# POWER_RTC.net
KiCad netlist of a schematic drawn in Altium Designer
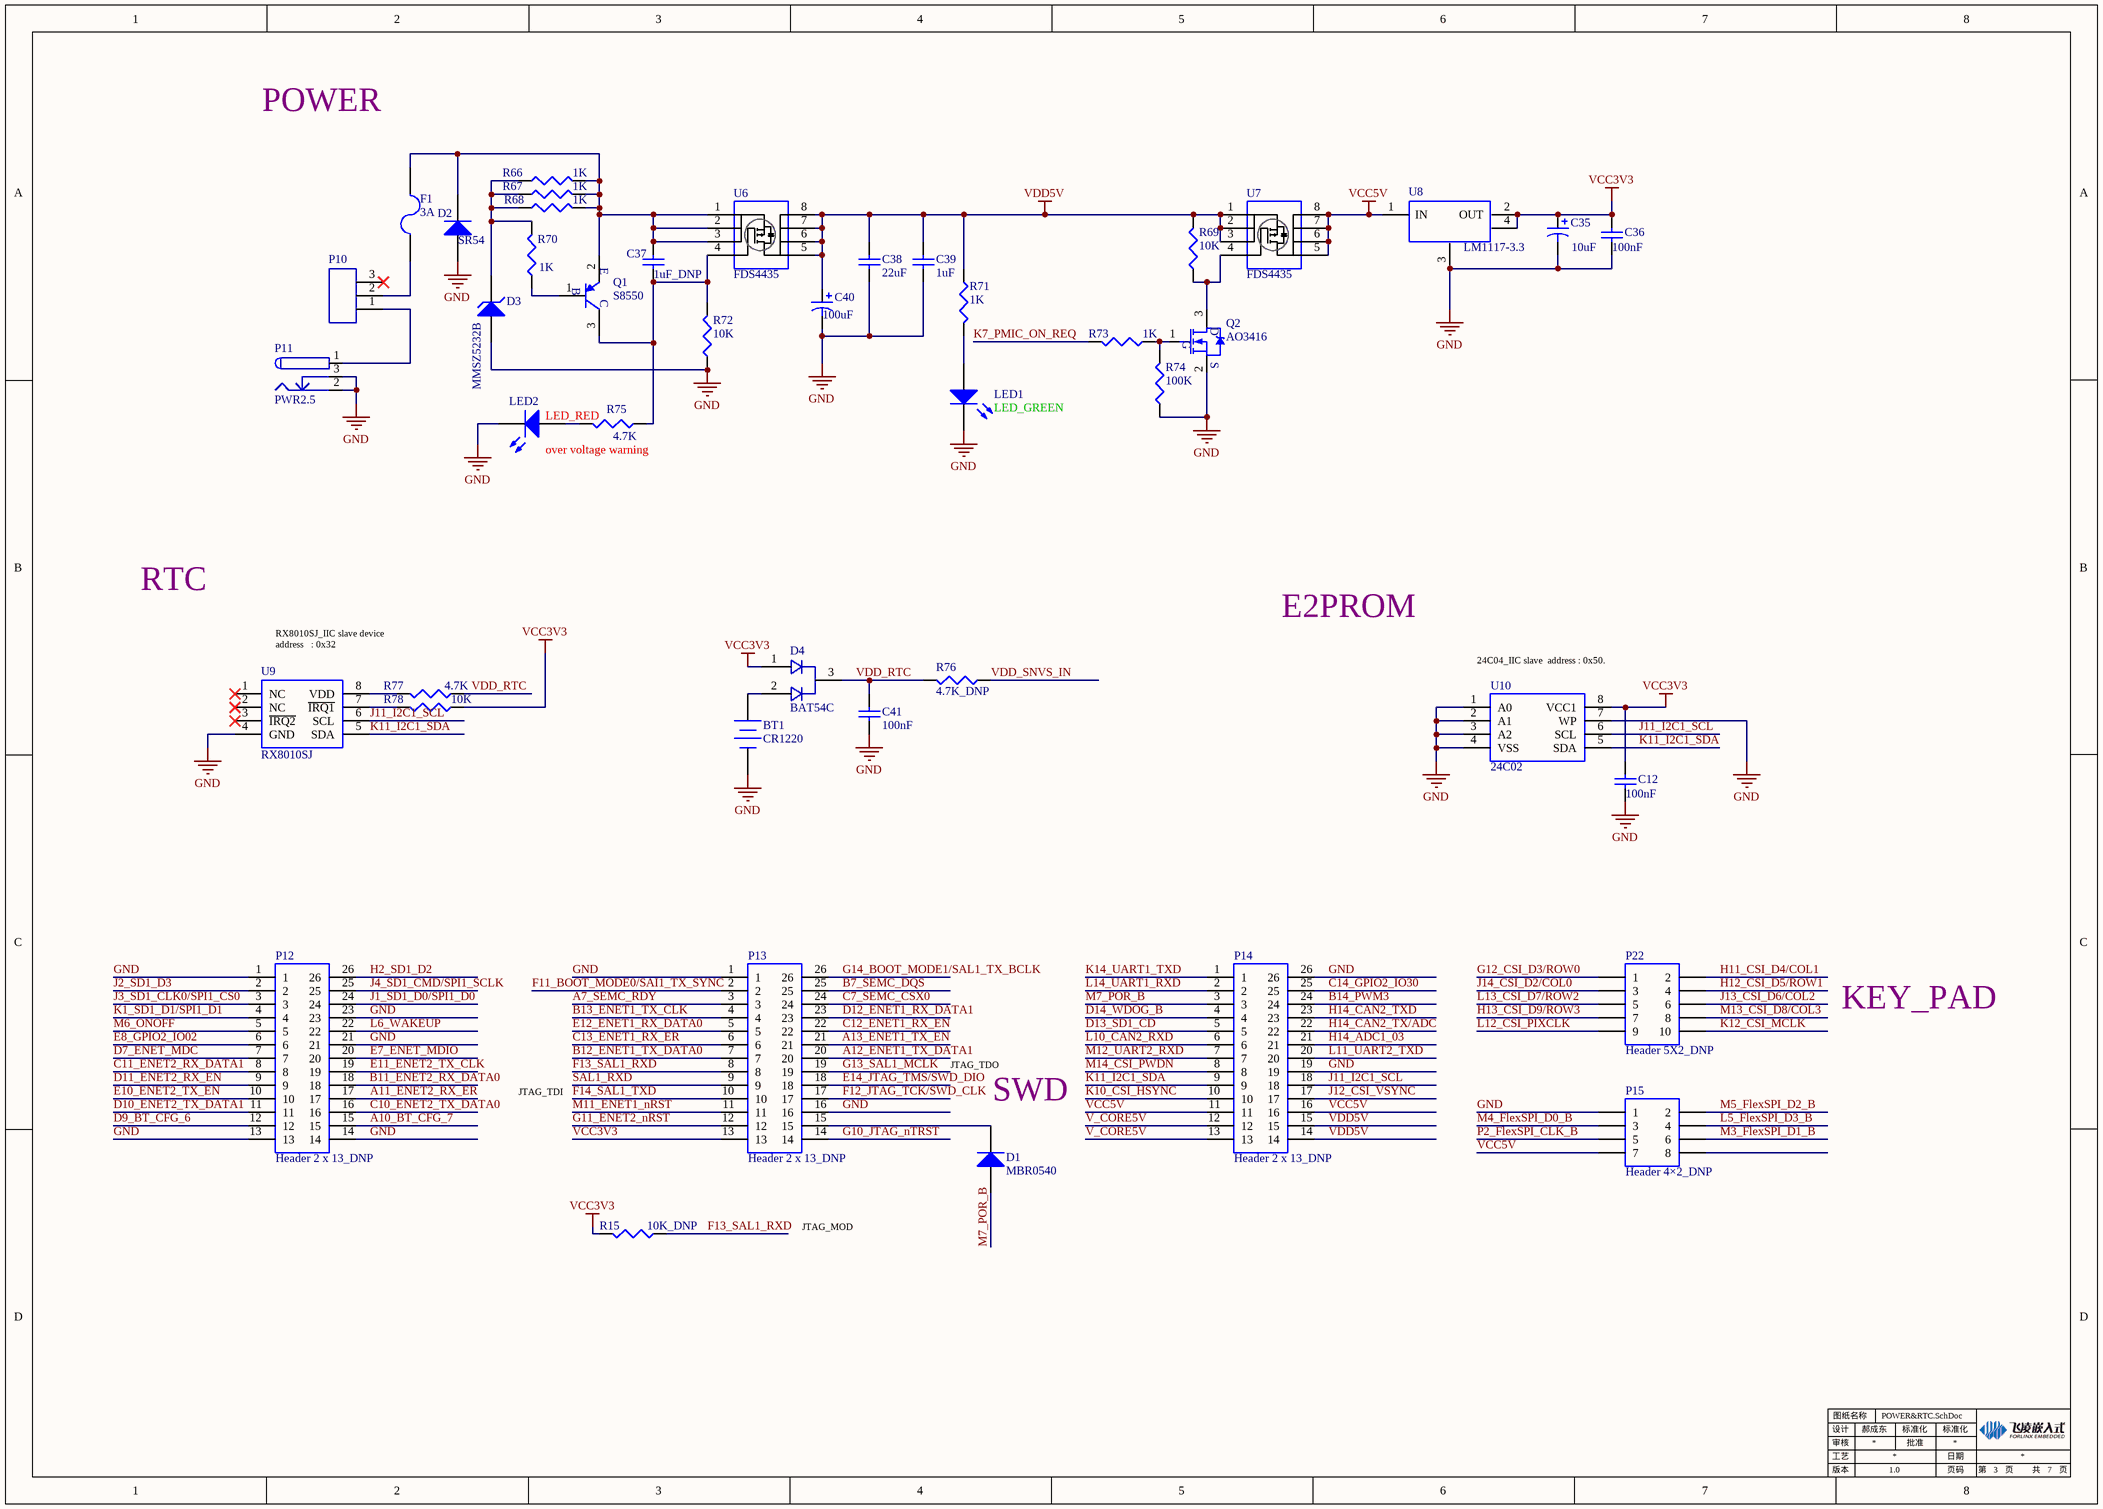
[diagram p0: POWER&RTC.SchDoc]

(export (version "E")
  (design (tool "Eeschema 10.0.6"))
  (components
    (comp (ref "BT1")
      (value "CR1220")
      (footprint "BH-1220 BATTERY")
      (description "Multicell Battery")
      (fields (field (name "PUBLISHER") "Altium Limited"))
      (libsource (lib "Miscellaneous Devices") (part "Battery"))
    )
    (comp (ref "C12")
      (value "100nF")
      (footprint "0603C+")
      (description "Capacitor")
      (fields (field (name "PUBLISHER") "Altium Limited"))
      (libsource (lib "Miscellaneous Devices") (part "Cap"))
    )
    (comp (ref "C35")
      (value "10uF")
      (footprint "TC3216A")
      (description "Polarized Capacitor (Radial)")
      (fields (field (name "PUBLISHER") "Altium Limited"))
      (libsource (lib "Miscellaneous Devices") (part "Cap Pol1"))
    )
    (comp (ref "C36")
      (value "100nF")
      (footprint "0603C+")
      (description "Capacitor")
      (fields (field (name "PUBLISHER") "Altium Limited"))
      (libsource (lib "Miscellaneous Devices") (part "Cap"))
    )
    (comp (ref "C37")
      (value "1uF_DNP")
      (footprint "0603C+")
      (description "Capacitor")
      (fields (field (name "PUBLISHER") "Altium Limited"))
      (libsource (lib "Miscellaneous Devices") (part "Cap"))
    )
    (comp (ref "C38")
      (value "22uF")
      (footprint "0603C+")
      (description "Capacitor")
      (fields (field (name "PUBLISHER") "Altium Limited"))
      (libsource (lib "Miscellaneous Devices") (part "Cap"))
    )
    (comp (ref "C39")
      (value "1uF")
      (footprint "0603C+")
      (description "Capacitor")
      (fields (field (name "PUBLISHER") "Altium Limited"))
      (libsource (lib "Miscellaneous Devices") (part "Cap"))
    )
    (comp (ref "C40")
      (value "100uF")
      (footprint "TC3528B")
      (description "Polarized Capacitor (Radial)")
      (fields (field (name "PUBLISHER") "Altium Limited"))
      (libsource (lib "Miscellaneous Devices") (part "Cap Pol1"))
    )
    (comp (ref "C41")
      (value "100nF")
      (footprint "0603C+")
      (description "Capacitor")
      (fields (field (name "PUBLISHER") "Altium Limited"))
      (libsource (lib "Miscellaneous Devices") (part "Cap"))
    )
    (comp (ref "D1")
      (value "MBR0540")
      (footprint "Diode1.6*2.6")
      (description "Default Diode")
      (fields (field (name "PUBLISHER") "Altium Limited"))
      (libsource (lib "Miscellaneous Devices") (part "Diode"))
    )
    (comp (ref "D2")
      (value "SR54")
      (footprint "SMB/DO-214AA")
      (description "Default Diode")
      (fields (field (name "PUBLISHER") "Altium Limited"))
      (libsource (lib "Miscellaneous Devices") (part "Diode"))
    )
    (comp (ref "D3")
      (value "MMSZ5232B")
      (footprint "Diode1.6*2.6")
      (description "Zener Diode")
      (fields (field (name "PUBLISHER") "Altium Limited"))
      (libsource (lib "Miscellaneous Devices") (part "D Zener"))
    )
    (comp (ref "D4") (value "BAT54C") (footprint "SOT23") (libsource (lib "Sch") (part "BAT54C")))
    (comp (ref "F1")
      (value "3A")
      (footprint "R_1210")
      (description "Fuse")
      (fields (field (name "PUBLISHER") "Altium Limited"))
      (libsource (lib "Miscellaneous Devices") (part "Fuse 2"))
    )
    (comp (ref "LED1")
      (value "LED_GREEN")
      (footprint "LED0603_M1608")
      (description "Typical RED, GREEN, YELLOW, AMBER GaAs LED")
      (fields (field (name "PUBLISHER") "Altium Limited"))
      (libsource (lib "Miscellaneous Devices") (part "LED2"))
    )
    (comp (ref "LED2")
      (value "LED_RED")
      (footprint "LED0603_M1608")
      (description "Typical RED, GREEN, YELLOW, AMBER GaAs LED")
      (fields (field (name "PUBLISHER") "Altium Limited"))
      (libsource (lib "Miscellaneous Devices") (part "LED2"))
    )
    (comp (ref "P10") (value "P18") (footprint "SW01") (libsource (lib "Sch") (part "CON3")))
    (comp (ref "P11") (value "PWR2.5") (footprint "JACK-2.5MM_B") (libsource (lib "Sch") (part "PWR2.5")))
    (comp (ref "P12")
      (value "Header 2 x 13_DNP")
      (footprint "HDR2X13")
      (libsource (lib "RT1060") (part "Header 2 x 13"))
    )
    (comp (ref "P13")
      (value "Header 2 x 13_DNP")
      (footprint "HDR2X13")
      (libsource (lib "RT1060") (part "Header 2 x 13"))
    )
    (comp (ref "P14")
      (value "Header 2 x 13_DNP")
      (footprint "HDR2X13")
      (libsource (lib "RT1060") (part "Header 2 x 13"))
    )
    (comp (ref "P15")
      (value "Header 4×2_DNP")
      (footprint "HDR2X4")
      (libsource (lib "RT1060") (part "Header 4×2"))
    )
    (comp (ref "P22")
      (value "Header 5X2_DNP")
      (footprint "HDR2X5")
      (description "Header, 5-Pin, Dual row")
      (fields (field (name "PUBLISHER") "Altium Limited"))
      (libsource (lib "RT1060") (part "Header 5X2"))
    )
    (comp (ref "Q1")
      (value "S8550")
      (footprint "SOT95P245X110-3N")
      (description "NPN Bipolar Transistor")
      (fields (field (name "PUBLISHER") "Altium Limited"))
      (libsource (lib "KQX6A") (part "PNP"))
    )
    (comp (ref "Q2")
      (value "AO3416")
      (footprint "SOT95P245X110-3N")
      (description "N-Channel Power MOSFET")
      (fields (field (name "PUBLISHER") "Altium Limited"))
      (libsource (lib "IMX6QP-C") (part "NMOS"))
    )
    (comp (ref "R15")
      (value "10K_DNP")
      (footprint "0603R+")
      (description "Resistor")
      (fields (field (name "PUBLISHER") "Altium Limited"))
      (libsource (lib "Miscellaneous Devices") (part "Res3"))
    )
    (comp (ref "R66")
      (value "1K")
      (footprint "0603R+")
      (description "Resistor")
      (fields (field (name "PUBLISHER") "Altium Limited"))
      (libsource (lib "Miscellaneous Devices") (part "Res3"))
    )
    (comp (ref "R67")
      (value "1K")
      (footprint "0603R+")
      (description "Resistor")
      (fields (field (name "PUBLISHER") "Altium Limited"))
      (libsource (lib "Miscellaneous Devices") (part "Res3"))
    )
    (comp (ref "R68")
      (value "1K")
      (footprint "0603R+")
      (description "Resistor")
      (fields (field (name "PUBLISHER") "Altium Limited"))
      (libsource (lib "Miscellaneous Devices") (part "Res3"))
    )
    (comp (ref "R69")
      (value "10K")
      (footprint "0603R+")
      (description "Resistor")
      (fields (field (name "PUBLISHER") "Altium Limited"))
      (libsource (lib "Miscellaneous Devices") (part "Res3"))
    )
    (comp (ref "R70")
      (value "1K")
      (footprint "0603R+")
      (description "Resistor")
      (fields (field (name "PUBLISHER") "Altium Limited"))
      (libsource (lib "Miscellaneous Devices") (part "Res3"))
    )
    (comp (ref "R71")
      (value "1K")
      (footprint "0603R+")
      (description "Resistor")
      (fields (field (name "PUBLISHER") "Altium Limited"))
      (libsource (lib "Miscellaneous Devices") (part "Res3"))
    )
    (comp (ref "R72")
      (value "10K")
      (footprint "0603R+")
      (description "Resistor")
      (fields (field (name "PUBLISHER") "Altium Limited"))
      (libsource (lib "Miscellaneous Devices") (part "Res3"))
    )
    (comp (ref "R73")
      (value "1K")
      (footprint "0603R+")
      (description "Resistor")
      (fields (field (name "PUBLISHER") "Altium Limited"))
      (libsource (lib "Miscellaneous Devices") (part "Res3"))
    )
    (comp (ref "R74")
      (value "100K")
      (footprint "0603R+")
      (description "Resistor")
      (fields (field (name "PUBLISHER") "Altium Limited"))
      (libsource (lib "Miscellaneous Devices") (part "Res3"))
    )
    (comp (ref "R75")
      (value "4.7K")
      (footprint "0603R+")
      (description "Resistor")
      (fields (field (name "PUBLISHER") "Altium Limited"))
      (libsource (lib "Miscellaneous Devices") (part "Res3"))
    )
    (comp (ref "R76")
      (value "4.7K_DNP")
      (footprint "0603R+")
      (description "Resistor")
      (fields (field (name "PUBLISHER") "Altium Limited"))
      (libsource (lib "Miscellaneous Devices") (part "Res3"))
    )
    (comp (ref "R77")
      (value "4.7K")
      (footprint "0603R+")
      (description "Resistor")
      (fields (field (name "PUBLISHER") "Altium Limited"))
      (libsource (lib "Miscellaneous Devices") (part "Res3"))
    )
    (comp (ref "R78")
      (value "10K")
      (footprint "0603R+")
      (description "Resistor")
      (fields (field (name "PUBLISHER") "Altium Limited"))
      (libsource (lib "Miscellaneous Devices") (part "Res3"))
    )
    (comp (ref "U6") (value "FDS4435") (footprint "FDS4435") (libsource (lib "OK5718") (part "FDS4435")))
    (comp (ref "U7") (value "FDS4435") (footprint "FDS4435") (libsource (lib "OK5718") (part "FDS4435")))
    (comp (ref "U8") (value "LM1117-3.3") (footprint "LM1117") (libsource (lib "Sch") (part "LM1117")))
    (comp (ref "U9") (value "RX8010SJ") (footprint "RX8010SJ") (libsource (lib "Sch") (part "RX8010SJ")))
    (comp (ref "U10")
      (value "24C02")
      (footprint "24C04_SO8")
      (libsource (lib "PCB_RT1052") (part "24C04_SO8"))
    )
  )
  (nets
    (net (code "1") (name "/A7_SEMC_RDY") (class "Default")
      (node (ref "P13") (pin "3") (pinfunction "3_3") (pintype "passive"))
    )
    (net (code "2") (name "/A10_BT_CFG_7") (class "Default")
      (node (ref "P12") (pin "15") (pinfunction "15_15") (pintype "passive"))
    )
    (net (code "3") (name "/A11_ENET2_RX_ER") (class "Default")
      (node (ref "P12") (pin "17") (pinfunction "17_17") (pintype "passive"))
    )
    (net (code "4") (name "/A12_ENET1_TX_DATA1") (class "Default")
      (node (ref "P13") (pin "20") (pinfunction "20_20") (pintype "passive"))
    )
    (net (code "5") (name "/A13_ENET1_TX_EN") (class "Default")
      (node (ref "P13") (pin "21") (pinfunction "21_21") (pintype "passive"))
    )
    (net (code "6") (name "/B7_SEMC_DQS") (class "Default")
      (node (ref "P13") (pin "25") (pinfunction "25_25") (pintype "passive"))
    )
    (net (code "7") (name "/B11_ENET2_RX_DATA0") (class "Default")
      (node (ref "P12") (pin "18") (pinfunction "18_18") (pintype "passive"))
    )
    (net (code "8") (name "/B12_ENET1_TX_DATA0") (class "Default")
      (node (ref "P13") (pin "7") (pinfunction "7_7") (pintype "passive"))
    )
    (net (code "9") (name "/B13_ENET1_TX_CLK") (class "Default")
      (node (ref "P13") (pin "4") (pinfunction "4_4") (pintype "passive"))
    )
    (net (code "10") (name "/B14_PWM3") (class "Default")
      (node (ref "P14") (pin "24") (pinfunction "24_24") (pintype "passive"))
    )
    (net (code "11") (name "/C7_SEMC_CSX0") (class "Default")
      (node (ref "P13") (pin "24") (pinfunction "24_24") (pintype "passive"))
    )
    (net (code "12") (name "/C10_ENET2_TX_DATA0") (class "Default")
      (node (ref "P12") (pin "16") (pinfunction "16_16") (pintype "passive"))
    )
    (net (code "13") (name "/C11_ENET2_RX_DATA1") (class "Default")
      (node (ref "P12") (pin "8") (pinfunction "8_8") (pintype "passive"))
    )
    (net (code "14") (name "/C12_ENET1_RX_EN") (class "Default")
      (node (ref "P13") (pin "22") (pinfunction "22_22") (pintype "passive"))
    )
    (net (code "15") (name "/C13_ENET1_RX_ER") (class "Default")
      (node (ref "P13") (pin "6") (pinfunction "6_6") (pintype "passive"))
    )
    (net (code "16") (name "/C14_GPIO2_IO30") (class "Default")
      (node (ref "P14") (pin "25") (pinfunction "25_25") (pintype "passive"))
    )
    (net (code "17") (name "/D7_ENET_MDC") (class "Default")
      (node (ref "P12") (pin "7") (pinfunction "7_7") (pintype "passive"))
    )
    (net (code "18") (name "/D9_BT_CFG_6") (class "Default")
      (node (ref "P12") (pin "12") (pinfunction "12_12") (pintype "passive"))
    )
    (net (code "19") (name "/D10_ENET2_TX_DATA1") (class "Default")
      (node (ref "P12") (pin "11") (pinfunction "11_11") (pintype "passive"))
    )
    (net (code "20") (name "/D11_ENET2_RX_EN") (class "Default")
      (node (ref "P12") (pin "9") (pinfunction "9_9") (pintype "passive"))
    )
    (net (code "21") (name "/D12_ENET1_RX_DATA1") (class "Default")
      (node (ref "P13") (pin "23") (pinfunction "23_23") (pintype "passive"))
    )
    (net (code "22") (name "/D13_SD1_CD") (class "Default")
      (node (ref "P14") (pin "5") (pinfunction "5_5") (pintype "passive"))
    )
    (net (code "23") (name "/D14_WDOG_B") (class "Default")
      (node (ref "P14") (pin "4") (pinfunction "4_4") (pintype "passive"))
    )
    (net (code "24") (name "/E7_ENET_MDIO") (class "Default")
      (node (ref "P12") (pin "20") (pinfunction "20_20") (pintype "passive"))
    )
    (net (code "25") (name "/E8_GPIO2_IO02") (class "Default")
      (node (ref "P12") (pin "6") (pinfunction "6_6") (pintype "passive"))
    )
    (net (code "26") (name "/E10_ENET2_TX_EN") (class "Default")
      (node (ref "P12") (pin "10") (pinfunction "10_10") (pintype "passive"))
    )
    (net (code "27") (name "/E11_ENET2_TX_CLK") (class "Default")
      (node (ref "P12") (pin "19") (pinfunction "19_19") (pintype "passive"))
    )
    (net (code "28") (name "/E12_ENET1_RX_DATA0") (class "Default")
      (node (ref "P13") (pin "5") (pinfunction "5_5") (pintype "passive"))
    )
    (net (code "29") (name "/E14_JTAG_TMS{slash}SWD_DIO") (class "Default")
      (node (ref "P13") (pin "18") (pinfunction "18_18") (pintype "passive"))
    )
    (net (code "30") (name "/F11_BOOT_MODE0{slash}SAI1_TX_SYNC") (class "Default")
      (node (ref "P13") (pin "2") (pinfunction "2_2") (pintype "passive"))
    )
    (net (code "31") (name "/F12_JTAG_TCK{slash}SWD_CLK") (class "Default")
      (node (ref "P13") (pin "17") (pinfunction "17_17") (pintype "passive"))
    )
    (net (code "32") (name "/F13_SAL1_RXD") (class "Default")
      (node (ref "P13") (pin "8") (pinfunction "8_8") (pintype "passive"))
      (node (ref "R15") (pin "1") (pinfunction "1_1") (pintype "passive"))
    )
    (net (code "33") (name "/F14_SAL1_TXD") (class "Default")
      (node (ref "P13") (pin "10") (pinfunction "10_10") (pintype "passive"))
    )
    (net (code "34") (name "/G10_JTAG_nTRST") (class "Default")
      (node (ref "P13") (pin "14") (pinfunction "14_14") (pintype "passive"))
    )
    (net (code "35") (name "/G11_ENET2_nRST") (class "Default")
      (node (ref "P13") (pin "12") (pinfunction "12_12") (pintype "passive"))
    )
    (net (code "36") (name "/G12_CSI_D3{slash}ROW0") (class "Default")
      (node (ref "P22") (pin "1") (pinfunction "1_1") (pintype "passive"))
    )
    (net (code "37") (name "/G13_SAL1_MCLK") (class "Default")
      (node (ref "P13") (pin "19") (pinfunction "19_19") (pintype "passive"))
    )
    (net (code "38") (name "/G14_BOOT_MODE1{slash}SAL1_TX_BCLK") (class "Default")
      (node (ref "P13") (pin "26") (pinfunction "26_26") (pintype "passive"))
    )
    (net (code "39") (name "/H2_SD1_D2") (class "Default")
      (node (ref "P12") (pin "26") (pinfunction "26_26") (pintype "passive"))
    )
    (net (code "40") (name "/H11_CSI_D4{slash}COL1") (class "Default")
      (node (ref "P22") (pin "2") (pinfunction "2_2") (pintype "passive"))
    )
    (net (code "41") (name "/H12_CSI_D5{slash}ROW1") (class "Default")
      (node (ref "P22") (pin "4") (pinfunction "4_4") (pintype "passive"))
    )
    (net (code "42") (name "/H13_CSI_D9{slash}ROW3") (class "Default")
      (node (ref "P22") (pin "7") (pinfunction "7_7") (pintype "passive"))
    )
    (net (code "43") (name "/H14_ADC1_03") (class "Default")
      (node (ref "P14") (pin "21") (pinfunction "21_21") (pintype "passive"))
    )
    (net (code "44") (name "/H14_CAN2_TXD") (class "Default")
      (node (ref "P14") (pin "23") (pinfunction "23_23") (pintype "passive"))
    )
    (net (code "45") (name "/H14_CAN2_TX{slash}ADC") (class "Default")
      (node (ref "P14") (pin "22") (pinfunction "22_22") (pintype "passive"))
    )
    (net (code "46") (name "/J1_SD1_D0{slash}SPI1_D0") (class "Default")
      (node (ref "P12") (pin "24") (pinfunction "24_24") (pintype "passive"))
    )
    (net (code "47") (name "/J2_SD1_D3") (class "Default")
      (node (ref "P12") (pin "2") (pinfunction "2_2") (pintype "passive"))
    )
    (net (code "48") (name "/J3_SD1_CLK0{slash}SPI1_CS0") (class "Default")
      (node (ref "P12") (pin "3") (pinfunction "3_3") (pintype "passive"))
    )
    (net (code "49") (name "/J4_SD1_CMD{slash}SPI1_SCLK") (class "Default")
      (node (ref "P12") (pin "25") (pinfunction "25_25") (pintype "passive"))
    )
    (net (code "50") (name "/J11_I2C1_SCL") (class "Default")
      (node (ref "P14") (pin "18") (pinfunction "18_18") (pintype "passive"))
      (node (ref "U10") (pin "6") (pinfunction "SCL_6") (pintype "passive"))
      (node (ref "U9") (pin "6") (pinfunction "SCL_6") (pintype "passive"))
    )
    (net (code "51") (name "/J12_CSI_VSYNC") (class "Default")
      (node (ref "P14") (pin "17") (pinfunction "17_17") (pintype "passive"))
    )
    (net (code "52") (name "/J13_CSI_D6{slash}COL2") (class "Default")
      (node (ref "P22") (pin "6") (pinfunction "6_6") (pintype "passive"))
    )
    (net (code "53") (name "/J14_CSI_D2{slash}COL0") (class "Default")
      (node (ref "P22") (pin "3") (pinfunction "3_3") (pintype "passive"))
    )
    (net (code "54") (name "/K1_SD1_D1{slash}SPI1_D1") (class "Default")
      (node (ref "P12") (pin "4") (pinfunction "4_4") (pintype "passive"))
    )
    (net (code "55") (name "/K7_PMIC_ON_REQ") (class "Default")
      (node (ref "R73") (pin "2") (pinfunction "2_2") (pintype "passive"))
    )
    (net (code "56") (name "/K10_CSI_HSYNC") (class "Default")
      (node (ref "P14") (pin "10") (pinfunction "10_10") (pintype "passive"))
    )
    (net (code "57") (name "/K11_I2C1_SDA") (class "Default")
      (node (ref "P14") (pin "9") (pinfunction "9_9") (pintype "passive"))
      (node (ref "U10") (pin "5") (pinfunction "SDA_5") (pintype "passive"))
      (node (ref "U9") (pin "5") (pinfunction "SDA_5") (pintype "passive"))
    )
    (net (code "58") (name "/K12_CSI_MCLK") (class "Default")
      (node (ref "P22") (pin "10") (pinfunction "10_10") (pintype "passive"))
    )
    (net (code "59") (name "/K14_UART1_TXD") (class "Default")
      (node (ref "P14") (pin "1") (pinfunction "1_1") (pintype "passive"))
    )
    (net (code "60") (name "/L5_FlexSPI_D3_B") (class "Default")
      (node (ref "P15") (pin "4") (pinfunction "4_4") (pintype "passive"))
    )
    (net (code "61") (name "/L6_WAKEUP") (class "Default")
      (node (ref "P12") (pin "22") (pinfunction "22_22") (pintype "passive"))
    )
    (net (code "62") (name "/L10_CAN2_RXD") (class "Default")
      (node (ref "P14") (pin "6") (pinfunction "6_6") (pintype "passive"))
    )
    (net (code "63") (name "/L11_UART2_TXD") (class "Default")
      (node (ref "P14") (pin "20") (pinfunction "20_20") (pintype "passive"))
    )
    (net (code "64") (name "/L12_CSI_PIXCLK") (class "Default")
      (node (ref "P22") (pin "9") (pinfunction "9_9") (pintype "passive"))
    )
    (net (code "65") (name "/L13_CSI_D7{slash}ROW2") (class "Default")
      (node (ref "P22") (pin "5") (pinfunction "5_5") (pintype "passive"))
    )
    (net (code "66") (name "/L14_UART1_RXD") (class "Default")
      (node (ref "P14") (pin "2") (pinfunction "2_2") (pintype "passive"))
    )
    (net (code "67") (name "/M3_FlexSPI_D1_B") (class "Default")
      (node (ref "P15") (pin "6") (pinfunction "6_6") (pintype "passive"))
    )
    (net (code "68") (name "/M4_FlexSPI_D0_B") (class "Default")
      (node (ref "P15") (pin "3") (pinfunction "3_3") (pintype "passive"))
    )
    (net (code "69") (name "/M5_FlexSPI_D2_B") (class "Default")
      (node (ref "P15") (pin "2") (pinfunction "2_2") (pintype "passive"))
    )
    (net (code "70") (name "/M6_ONOFF") (class "Default")
      (node (ref "P12") (pin "5") (pinfunction "5_5") (pintype "passive"))
    )
    (net (code "71") (name "/M7_POR_B") (class "Default")
      (node (ref "D1") (pin "1") (pinfunction "A_1") (pintype "passive"))
      (node (ref "P14") (pin "3") (pinfunction "3_3") (pintype "passive"))
    )
    (net (code "72") (name "/M11_ENET1_nRST") (class "Default")
      (node (ref "P13") (pin "11") (pinfunction "11_11") (pintype "passive"))
    )
    (net (code "73") (name "/M12_UART2_RXD") (class "Default")
      (node (ref "P14") (pin "7") (pinfunction "7_7") (pintype "passive"))
    )
    (net (code "74") (name "/M13_CSI_D8{slash}COL3") (class "Default")
      (node (ref "P22") (pin "8") (pinfunction "8_8") (pintype "passive"))
    )
    (net (code "75") (name "/M14_CSI_PWDN") (class "Default")
      (node (ref "P14") (pin "8") (pinfunction "8_8") (pintype "passive"))
    )
    (net (code "76") (name "/P2_FlexSPI_CLK_B") (class "Default")
      (node (ref "P15") (pin "5") (pinfunction "5_5") (pintype "passive"))
    )
    (net (code "77") (name "/SAL1_RXD") (class "Default")
      (node (ref "P13") (pin "9") (pinfunction "9_9") (pintype "passive"))
    )
    (net (code "78") (name "/VDD_RTC") (class "Default")
      (node (ref "C41") (pin "2") (pinfunction "2_2") (pintype "passive"))
      (node (ref "D4") (pin "3") (pintype "passive"))
      (node (ref "R76") (pin "2") (pinfunction "2_2") (pintype "passive"))
      (node (ref "R77") (pin "1") (pinfunction "1_1") (pintype "passive"))
    )
    (net (code "79") (name "/VDD_SNVS_IN") (class "Default")
      (node (ref "R76") (pin "1") (pinfunction "1_1") (pintype "passive"))
    )
    (net (code "80") (name "/V_CORE5V") (class "Default")
      (node (ref "P14") (pin "12") (pinfunction "12_12") (pintype "passive"))
      (node (ref "P14") (pin "13") (pinfunction "13_13") (pintype "passive"))
    )
    (net (code "81") (name "GND") (class "Default")
      (node (ref "BT1") (pin "2") (pinfunction "-_2") (pintype "passive"))
      (node (ref "C12") (pin "1") (pinfunction "1_1") (pintype "passive"))
      (node (ref "C35") (pin "2") (pinfunction "2_2") (pintype "passive"))
      (node (ref "C36") (pin "1") (pinfunction "1_1") (pintype "passive"))
      (node (ref "C38") (pin "2") (pinfunction "2_2") (pintype "passive"))
      (node (ref "C39") (pin "2") (pinfunction "2_2") (pintype "passive"))
      (node (ref "C40") (pin "2") (pinfunction "2_2") (pintype "passive"))
      (node (ref "C41") (pin "1") (pinfunction "1_1") (pintype "passive"))
      (node (ref "D2") (pin "1") (pinfunction "A_1") (pintype "passive"))
      (node (ref "D3") (pin "1") (pinfunction "A_1") (pintype "passive"))
      (node (ref "LED1") (pin "2") (pinfunction "K_2") (pintype "passive"))
      (node (ref "LED2") (pin "2") (pinfunction "K_2") (pintype "passive"))
      (node (ref "P11") (pin "2") (pinfunction "ADJ_2") (pintype "passive"))
      (node (ref "P11") (pin "3") (pinfunction "ADJ_3") (pintype "passive"))
      (node (ref "P12") (pin "1") (pinfunction "1_1") (pintype "passive"))
      (node (ref "P12") (pin "13") (pinfunction "13_13") (pintype "passive"))
      (node (ref "P12") (pin "14") (pinfunction "14_14") (pintype "passive"))
      (node (ref "P12") (pin "21") (pinfunction "21_21") (pintype "passive"))
      (node (ref "P12") (pin "23") (pinfunction "23_23") (pintype "passive"))
      (node (ref "P13") (pin "1") (pinfunction "1_1") (pintype "passive"))
      (node (ref "P13") (pin "16") (pinfunction "16_16") (pintype "passive"))
      (node (ref "P14") (pin "19") (pinfunction "19_19") (pintype "passive"))
      (node (ref "P14") (pin "26") (pinfunction "26_26") (pintype "passive"))
      (node (ref "P15") (pin "1") (pinfunction "1_1") (pintype "passive"))
      (node (ref "Q2") (pin "2") (pinfunction "S_2") (pintype "passive"))
      (node (ref "R72") (pin "1") (pinfunction "1_1") (pintype "passive"))
      (node (ref "R74") (pin "1") (pinfunction "1_1") (pintype "passive"))
      (node (ref "U10") (pin "1") (pinfunction "A0_1") (pintype "passive"))
      (node (ref "U10") (pin "2") (pinfunction "A1_2") (pintype "passive"))
      (node (ref "U10") (pin "3") (pinfunction "A2_3") (pintype "passive"))
      (node (ref "U10") (pin "4") (pinfunction "VSS_4") (pintype "passive"))
      (node (ref "U10") (pin "7") (pinfunction "WP_7") (pintype "passive"))
      (node (ref "U8") (pin "3") (pinfunction "GND_3") (pintype "passive"))
      (node (ref "U9") (pin "4") (pinfunction "GND_4") (pintype "passive"))
    )
    (net (code "82") (name "Net-(BT1-+)") (class "Default")
      (node (ref "BT1") (pin "1") (pinfunction "+_1") (pintype "passive"))
      (node (ref "D4") (pin "2") (pinfunction "2_2") (pintype "passive"))
    )
    (net (code "83") (name "Net-(D1-K)") (class "Default")
      (node (ref "D1") (pin "2") (pinfunction "K_2") (pintype "passive"))
      (node (ref "P13") (pin "15") (pinfunction "15_15") (pintype "passive"))
    )
    (net (code "84") (name "Net-(D2-K)") (class "Default")
      (node (ref "C37") (pin "1") (pinfunction "1_1") (pintype "passive"))
      (node (ref "D2") (pin "2") (pinfunction "K_2") (pintype "passive"))
      (node (ref "F1") (pin "2") (pinfunction "2_2") (pintype "passive"))
      (node (ref "Q1") (pin "2") (pinfunction "E_2") (pintype "passive"))
      (node (ref "R66") (pin "2") (pinfunction "2_2") (pintype "passive"))
      (node (ref "R67") (pin "2") (pinfunction "2_2") (pintype "passive"))
      (node (ref "R68") (pin "2") (pinfunction "2_2") (pintype "passive"))
      (node (ref "U6") (pin "1") (pinfunction "S_1") (pintype "passive"))
      (node (ref "U6") (pin "2") (pinfunction "S_2") (pintype "passive"))
      (node (ref "U6") (pin "3") (pinfunction "S_3") (pintype "passive"))
    )
    (net (code "85") (name "Net-(D3-K)") (class "Default")
      (node (ref "D3") (pin "2") (pinfunction "K_2") (pintype "passive"))
      (node (ref "R66") (pin "1") (pinfunction "1_1") (pintype "passive"))
      (node (ref "R67") (pin "1") (pinfunction "1_1") (pintype "passive"))
      (node (ref "R68") (pin "1") (pinfunction "1_1") (pintype "passive"))
      (node (ref "R70") (pin "2") (pinfunction "2_2") (pintype "passive"))
    )
    (net (code "86") (name "Net-(LED1-A)") (class "Default")
      (node (ref "LED1") (pin "1") (pinfunction "A_1") (pintype "passive"))
      (node (ref "R71") (pin "2") (pinfunction "2_2") (pintype "passive"))
    )
    (net (code "87") (name "Net-(LED2-A)") (class "Default")
      (node (ref "LED2") (pin "1") (pinfunction "A_1") (pintype "passive"))
      (node (ref "R75") (pin "2") (pinfunction "2_2") (pintype "passive"))
    )
    (net (code "88") (name "Net-(P10-DQ16)") (class "Default")
      (node (ref "P10") (pin "1") (pinfunction "DQ16_1") (pintype "passive"))
      (node (ref "P11") (pin "1") (pinfunction "ADJ_1") (pintype "passive"))
    )
    (net (code "89") (name "Net-(P10-DQ17)") (class "Default")
      (node (ref "F1") (pin "1") (pinfunction "1_1") (pintype "passive"))
      (node (ref "P10") (pin "2") (pinfunction "DQ17_2") (pintype "passive"))
    )
    (net (code "90") (name "Net-(Q1-B)") (class "Default")
      (node (ref "Q1") (pin "1") (pinfunction "B_1") (pintype "passive"))
      (node (ref "R70") (pin "1") (pinfunction "1_1") (pintype "passive"))
    )
    (net (code "91") (name "Net-(Q1-C)") (class "Default")
      (node (ref "C37") (pin "2") (pinfunction "2_2") (pintype "passive"))
      (node (ref "Q1") (pin "3") (pinfunction "C_3") (pintype "passive"))
      (node (ref "R72") (pin "2") (pinfunction "2_2") (pintype "passive"))
      (node (ref "R75") (pin "1") (pinfunction "1_1") (pintype "passive"))
      (node (ref "U6") (pin "4") (pinfunction "G_4") (pintype "passive"))
    )
    (net (code "92") (name "Net-(Q2-D)") (class "Default")
      (node (ref "Q2") (pin "3") (pinfunction "D_3") (pintype "passive"))
      (node (ref "R69") (pin "1") (pinfunction "1_1") (pintype "passive"))
      (node (ref "U7") (pin "4") (pinfunction "G_4") (pintype "passive"))
    )
    (net (code "93") (name "Net-(Q2-G)") (class "Default")
      (node (ref "Q2") (pin "1") (pinfunction "G_1") (pintype "passive"))
      (node (ref "R73") (pin "1") (pinfunction "1_1") (pintype "passive"))
      (node (ref "R74") (pin "2") (pinfunction "2_2") (pintype "passive"))
    )
    (net (code "94") (name "Net-(U9-VDD)") (class "Default")
      (node (ref "R77") (pin "2") (pinfunction "2_2") (pintype "passive"))
      (node (ref "U9") (pin "8") (pinfunction "VDD_8") (pintype "passive"))
    )
    (net (code "95") (name "Net-(U9-~{IRQ1})") (class "Default")
      (node (ref "R78") (pin "2") (pinfunction "2_2") (pintype "passive"))
      (node (ref "U9") (pin "7") (pinfunction "~{IRQ1}_7") (pintype "passive"))
    )
    (net (code "96") (name "VCC3V3") (class "Default")
      (node (ref "C12") (pin "2") (pinfunction "2_2") (pintype "passive"))
      (node (ref "C35") (pin "1") (pinfunction "1_1") (pintype "passive"))
      (node (ref "C36") (pin "2") (pinfunction "2_2") (pintype "passive"))
      (node (ref "D4") (pin "1") (pinfunction "1_1") (pintype "passive"))
      (node (ref "P13") (pin "13") (pinfunction "13_13") (pintype "passive"))
      (node (ref "R15") (pin "2") (pinfunction "2_2") (pintype "passive"))
      (node (ref "R78") (pin "1") (pinfunction "1_1") (pintype "passive"))
      (node (ref "U10") (pin "8") (pinfunction "VCC1_8") (pintype "passive"))
      (node (ref "U8") (pin "2") (pinfunction "OUT_2") (pintype "passive"))
      (node (ref "U8") (pin "4") (pintype "passive"))
    )
    (net (code "97") (name "VCC5V") (class "Default")
      (node (ref "P14") (pin "11") (pinfunction "11_11") (pintype "passive"))
      (node (ref "P14") (pin "16") (pinfunction "16_16") (pintype "passive"))
      (node (ref "P15") (pin "7") (pinfunction "7_7") (pintype "passive"))
      (node (ref "U7") (pin "5") (pinfunction "D_5") (pintype "passive"))
      (node (ref "U7") (pin "6") (pinfunction "D_6") (pintype "passive"))
      (node (ref "U7") (pin "7") (pinfunction "D_7") (pintype "passive"))
      (node (ref "U7") (pin "8") (pinfunction "D_8") (pintype "passive"))
      (node (ref "U8") (pin "1") (pinfunction "IN_1") (pintype "passive"))
    )
    (net (code "98") (name "VDD5V") (class "Default")
      (node (ref "C38") (pin "1") (pinfunction "1_1") (pintype "passive"))
      (node (ref "C39") (pin "1") (pinfunction "1_1") (pintype "passive"))
      (node (ref "C40") (pin "1") (pinfunction "1_1") (pintype "passive"))
      (node (ref "P14") (pin "14") (pinfunction "14_14") (pintype "passive"))
      (node (ref "P14") (pin "15") (pinfunction "15_15") (pintype "passive"))
      (node (ref "R69") (pin "2") (pinfunction "2_2") (pintype "passive"))
      (node (ref "R71") (pin "1") (pinfunction "1_1") (pintype "passive"))
      (node (ref "U6") (pin "5") (pinfunction "D_5") (pintype "passive"))
      (node (ref "U6") (pin "6") (pinfunction "D_6") (pintype "passive"))
      (node (ref "U6") (pin "7") (pinfunction "D_7") (pintype "passive"))
      (node (ref "U6") (pin "8") (pinfunction "D_8") (pintype "passive"))
      (node (ref "U7") (pin "1") (pinfunction "S_1") (pintype "passive"))
      (node (ref "U7") (pin "2") (pinfunction "S_2") (pintype "passive"))
      (node (ref "U7") (pin "3") (pinfunction "S_3") (pintype "passive"))
    )
    (net (code "99") (name "unconnected-(P10-DQ18-Pad3)") (class "Default")
      (node (ref "P10") (pin "3") (pinfunction "DQ18_3") (pintype "passive+no_connect"))
    )
    (net (code "100") (name "unconnected-(P15-Pad8)") (class "Default")
      (node (ref "P15") (pin "8") (pinfunction "8_8") (pintype "passive"))
    )
    (net (code "101") (name "unconnected-(U9-NC-Pad1)") (class "Default")
      (node (ref "U9") (pin "1") (pinfunction "NC_1") (pintype "passive+no_connect"))
    )
    (net (code "102") (name "unconnected-(U9-NC-Pad2)") (class "Default")
      (node (ref "U9") (pin "2") (pinfunction "NC_2") (pintype "passive+no_connect"))
    )
    (net (code "103") (name "unconnected-(U9-~{IRQ2}-Pad3)") (class "Default")
      (node (ref "U9") (pin "3") (pinfunction "~{IRQ2}_3") (pintype "passive+no_connect"))
    )
  )
)
